# TMS320F28379D_ADC.net
KiCad netlist of a schematic drawn in Altium Designer
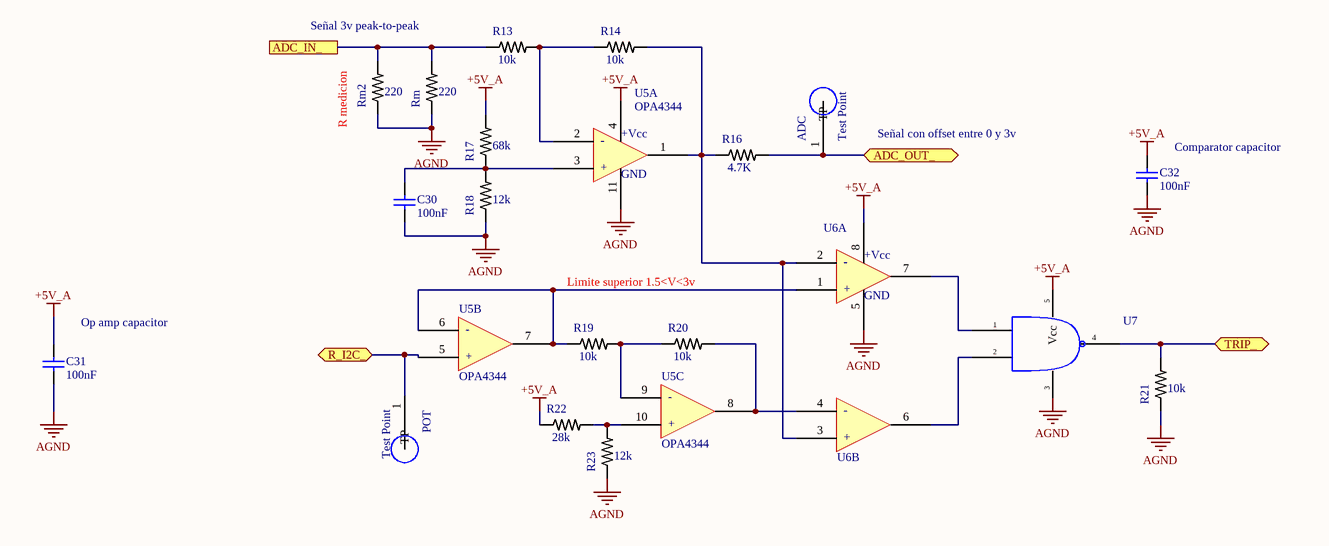
[diagram p0: TMS320F28379D_ADC.SchDoc]

(export (version "E")
  (design (tool "Eeschema 10.0.6"))
  (components
    (comp (ref "ADC")
      (value "Test Point")
      (footprint "Test point")
      (description "Surface Mount Test Points")
      (fields
        (field (name "DIGI-KEY PART NUMBER") "A106146CT-ND")
        (field (name "MANUFACTURER PART NUMBER") "RCW-0C")
      )
      (libsource (lib "Conectores") (part "Test Point"))
    )
    (comp (ref "C30")
      (value "100nF")
      (footprint "CAP 0805")
      (fields (field (name "Comment") "Cap cerámico"))
      (libsource (lib "Condensadores") (part "Cap cerámico"))
    )
    (comp (ref "C31")
      (value "100nF")
      (footprint "CAP 0805")
      (fields (field (name "Comment") "Cap cerámico"))
      (libsource (lib "Condensadores") (part "Cap cerámico"))
    )
    (comp (ref "C32")
      (value "100nF")
      (footprint "CAP 0805")
      (fields (field (name "Comment") "Cap cerámico"))
      (libsource (lib "Condensadores") (part "Cap cerámico"))
    )
    (comp (ref "POT")
      (value "Test Point")
      (footprint "Test point")
      (description "Surface Mount Test Points")
      (fields
        (field (name "DIGI-KEY PART NUMBER") "A106146CT-ND")
        (field (name "MANUFACTURER PART NUMBER") "RCW-0C")
      )
      (libsource (lib "Conectores") (part "Test Point"))
    )
    (comp (ref "R13")
      (value "10k")
      (footprint "Resistor 0805")
      (description "Resistor")
      (fields (field (name "Comment") "Resistor 0805"))
      (libsource (lib "Resistencias") (part "Resistor"))
    )
    (comp (ref "R14")
      (value "10k")
      (footprint "Resistor 0805")
      (description "Resistor")
      (fields (field (name "Comment") "Resistor 0805"))
      (libsource (lib "Resistencias") (part "Resistor"))
    )
    (comp (ref "R16")
      (value "4.7K")
      (footprint "Resistor 0805")
      (description "Resistor")
      (fields (field (name "Comment") "Resistor 0805"))
      (libsource (lib "Resistencias") (part "Resistor"))
    )
    (comp (ref "R17")
      (value "68k")
      (footprint "Resistor 0805")
      (description "Resistor")
      (fields (field (name "Comment") "Resistor 0805"))
      (libsource (lib "Resistencias") (part "Resistor"))
    )
    (comp (ref "R18")
      (value "12k")
      (footprint "Resistor 0805")
      (description "Resistor")
      (fields (field (name "Comment") "Resistor 0805"))
      (libsource (lib "Resistencias") (part "Resistor"))
    )
    (comp (ref "R19")
      (value "10k")
      (footprint "Resistor 0805")
      (description "Resistor")
      (fields (field (name "Comment") "Resistor 0805"))
      (libsource (lib "Resistencias") (part "Resistor"))
    )
    (comp (ref "R20")
      (value "10k")
      (footprint "Resistor 0805")
      (description "Resistor")
      (fields (field (name "Comment") "Resistor 0805"))
      (libsource (lib "Resistencias") (part "Resistor"))
    )
    (comp (ref "R21")
      (value "10k")
      (footprint "Resistor 0805")
      (description "Resistor")
      (fields (field (name "Comment") "Resistor 0805"))
      (libsource (lib "Resistencias") (part "Resistor"))
    )
    (comp (ref "R22")
      (value "28k")
      (footprint "Resistor 0805")
      (description "Resistor")
      (fields (field (name "Comment") "Resistor 0805"))
      (libsource (lib "Resistencias") (part "Resistor"))
    )
    (comp (ref "R23")
      (value "12k")
      (footprint "Resistor 0805")
      (description "Resistor")
      (fields (field (name "Comment") "Resistor 0805"))
      (libsource (lib "Resistencias") (part "Resistor"))
    )
    (comp (ref "Rm")
      (value "220")
      (footprint "Resistor 0805")
      (description "Resistor")
      (fields
        (field (name "DIGI-KEY PART NUMBER") "RCL220ACT-ND")
        (field (name "MANUFACTURER PART NUMBER") "RCL1218220RFKEK")
      )
      (libsource (lib "Resistencias") (part "Resistor"))
    )
    (comp (ref "Rm2")
      (value "220")
      (footprint "Resistor 0805")
      (description "Resistor")
      (fields
        (field (name "DIGI-KEY PART NUMBER") "RCL220ACT-ND")
        (field (name "MANUFACTURER PART NUMBER") "RCL1218220RFKEK")
      )
      (libsource (lib "Resistencias") (part "Resistor"))
    )
    (comp (ref "U5")
      (value "OPA4344")
      (footprint "14-TSSOP")
      (fields
        (field (name "DIGI-KEY PART NUMBER") "OPA4344EACT-ND")
        (field (name "MANUFACTURER PART NUMBER") "OPA4344EA/250")
      )
      (libsource (lib "Circuitos integrados") (part "OPA4344"))
    )
    (comp (ref "U6")
      (value "MAX962")
      (footprint "8-TSSOP")
      (fields
        (field (name "DIGI-KEY PART NUMBER") "MAX962EUA+-ND")
        (field (name "MANUFACTURER PART NUMBER") "MAX962EUA+")
      )
      (libsource (lib "Circuitos integrados") (part "MAX962"))
    )
    (comp (ref "U7")
      (value "SN74LVC1G00DBVR")
      (footprint "SOT-553")
      (description "IC GATE NAND 1CH 2-INP")
      (fields
        (field (name "DIGI-KEY PART NUMBER") "M74VHC1GT00DFT1GOSCT-ND")
        (field (name "MANUFACTURER PART NUMBER") "M74VHC1GT00DFT1G")
      )
      (libsource (lib "Circuitos integrados") (part "SN74LVC1G00DBVR"))
    )
  )
  (nets
    (net (code "1") (name "+5V_A") (class "Default")
      (node (ref "C31") (pin "2") (pinfunction "2_2") (pintype "passive"))
      (node (ref "C32") (pin "1") (pinfunction "1_1") (pintype "passive"))
      (node (ref "R17") (pin "2") (pinfunction "2_2") (pintype "passive"))
      (node (ref "R22") (pin "1") (pinfunction "1_1") (pintype "passive"))
      (node (ref "U5") (pin "4") (pinfunction "v+_4") (pintype "passive"))
      (node (ref "U6") (pin "8") (pinfunction "VCC_8") (pintype "passive"))
      (node (ref "U7") (pin "5") (pinfunction "Vcc_5") (pintype "passive"))
    )
    (net (code "2") (name "/ADC_IN_") (class "Default")
      (node (ref "R13") (pin "1") (pinfunction "1_1") (pintype "passive"))
      (node (ref "Rm") (pin "2") (pinfunction "2_2") (pintype "passive"))
      (node (ref "Rm2") (pin "2") (pinfunction "2_2") (pintype "passive"))
    )
    (net (code "3") (name "/ADC_OUT_") (class "Default")
      (node (ref "ADC") (pin "1") (pinfunction "TP_1") (pintype "passive"))
      (node (ref "R16") (pin "2") (pinfunction "2_2") (pintype "passive"))
    )
    (net (code "4") (name "/R_I2C_") (class "Default")
      (node (ref "POT") (pin "1") (pinfunction "TP_1") (pintype "passive"))
      (node (ref "U5") (pin "5") (pinfunction "+in_b_5") (pintype "passive"))
    )
    (net (code "5") (name "/TRIP_") (class "Default")
      (node (ref "R21") (pin "2") (pinfunction "2_2") (pintype "passive"))
      (node (ref "U7") (pin "4") (pinfunction "4_4") (pintype "passive"))
    )
    (net (code "6") (name "AGND") (class "Default")
      (node (ref "C30") (pin "1") (pinfunction "1_1") (pintype "passive"))
      (node (ref "C31") (pin "1") (pinfunction "1_1") (pintype "passive"))
      (node (ref "C32") (pin "2") (pinfunction "2_2") (pintype "passive"))
      (node (ref "R18") (pin "1") (pinfunction "1_1") (pintype "passive"))
      (node (ref "R21") (pin "1") (pinfunction "1_1") (pintype "passive"))
      (node (ref "R23") (pin "1") (pinfunction "1_1") (pintype "passive"))
      (node (ref "Rm") (pin "1") (pinfunction "1_1") (pintype "passive"))
      (node (ref "Rm2") (pin "1") (pinfunction "1_1") (pintype "passive"))
      (node (ref "U5") (pin "11") (pinfunction "v-_11") (pintype "passive"))
      (node (ref "U6") (pin "5") (pinfunction "GND_5") (pintype "passive"))
      (node (ref "U7") (pin "3") (pinfunction "GND_3") (pintype "passive"))
    )
    (net (code "7") (name "Net-(U5A-+in_a)") (class "Default")
      (node (ref "C30") (pin "2") (pinfunction "2_2") (pintype "passive"))
      (node (ref "R17") (pin "1") (pinfunction "1_1") (pintype "passive"))
      (node (ref "R18") (pin "2") (pinfunction "2_2") (pintype "passive"))
      (node (ref "U5") (pin "3") (pinfunction "+in_a_3") (pintype "passive"))
    )
    (net (code "8") (name "Net-(U5A--in_a)") (class "Default")
      (node (ref "R13") (pin "2") (pinfunction "2_2") (pintype "passive"))
      (node (ref "R14") (pin "1") (pinfunction "1_1") (pintype "passive"))
      (node (ref "U5") (pin "2") (pinfunction "-in_a_2") (pintype "passive"))
    )
    (net (code "9") (name "Net-(U5A-out_a)") (class "Default")
      (node (ref "R14") (pin "2") (pinfunction "2_2") (pintype "passive"))
      (node (ref "R16") (pin "1") (pinfunction "1_1") (pintype "passive"))
      (node (ref "U5") (pin "1") (pinfunction "out_a_1") (pintype "passive"))
      (node (ref "U6") (pin "2") (pinfunction "-in_a_2") (pintype "passive"))
      (node (ref "U6") (pin "3") (pinfunction "+IN_B_3") (pintype "passive"))
    )
    (net (code "10") (name "Net-(U5B--in_b)") (class "Default")
      (node (ref "R19") (pin "1") (pinfunction "1_1") (pintype "passive"))
      (node (ref "U5") (pin "6") (pinfunction "-in_b_6") (pintype "passive"))
      (node (ref "U5") (pin "7") (pinfunction "out_b_7") (pintype "passive"))
      (node (ref "U6") (pin "1") (pinfunction "+in_a_1") (pintype "passive"))
    )
    (net (code "11") (name "Net-(U5C-+in_c)") (class "Default")
      (node (ref "R22") (pin "2") (pinfunction "2_2") (pintype "passive"))
      (node (ref "R23") (pin "2") (pinfunction "2_2") (pintype "passive"))
      (node (ref "U5") (pin "10") (pinfunction "+in_c_10") (pintype "passive"))
    )
    (net (code "12") (name "Net-(U5C--in_c)") (class "Default")
      (node (ref "R19") (pin "2") (pinfunction "2_2") (pintype "passive"))
      (node (ref "R20") (pin "1") (pinfunction "1_1") (pintype "passive"))
      (node (ref "U5") (pin "9") (pinfunction "-in_c_9") (pintype "passive"))
    )
    (net (code "13") (name "Net-(U5C-out_c)") (class "Default")
      (node (ref "R20") (pin "2") (pinfunction "2_2") (pintype "passive"))
      (node (ref "U5") (pin "8") (pinfunction "out_c_8") (pintype "passive"))
      (node (ref "U6") (pin "4") (pinfunction "-IN_B_4") (pintype "passive"))
    )
    (net (code "14") (name "Net-(U6A-out_a)") (class "Default")
      (node (ref "U6") (pin "7") (pinfunction "out_a_7") (pintype "passive"))
      (node (ref "U7") (pin "1") (pinfunction "1_1") (pintype "passive"))
    )
    (net (code "15") (name "Net-(U6B-OUT_B)") (class "Default")
      (node (ref "U6") (pin "6") (pinfunction "OUT_B_6") (pintype "passive"))
      (node (ref "U7") (pin "2") (pinfunction "2_2") (pintype "passive"))
    )
  )
)
